# FOC_STM32G431.net
KiCad netlist of a schematic drawn in Altium Designer
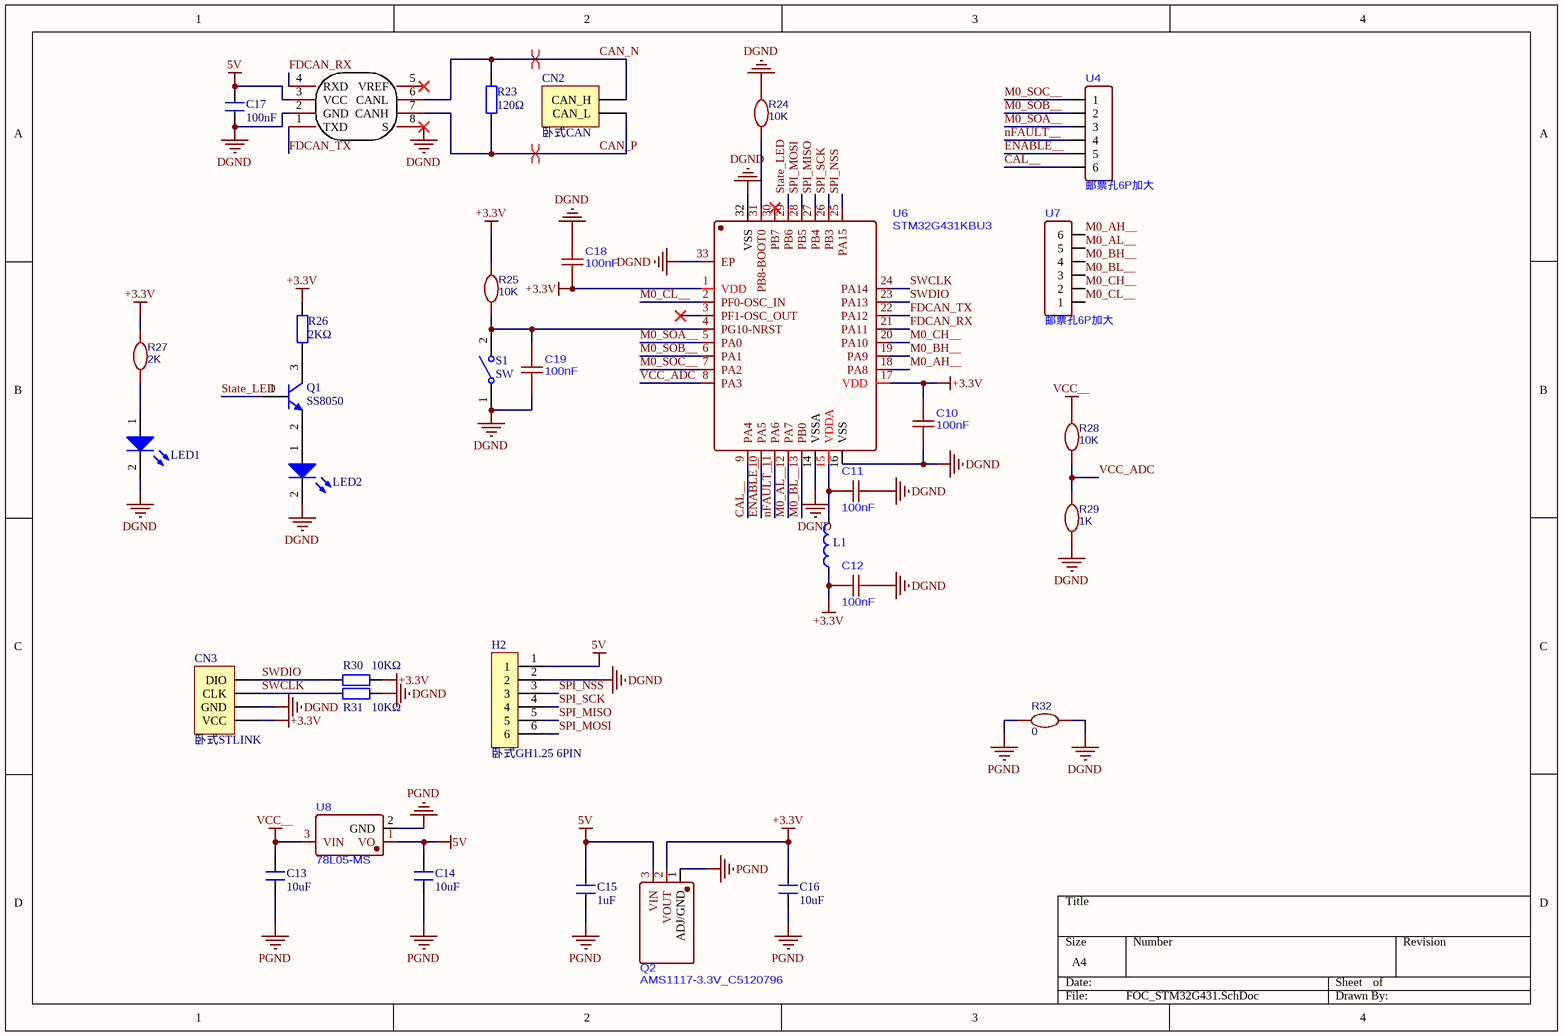
[diagram p0: FOC_STM32G431.SchDoc]

(export (version "E")
  (design (tool "Eeschema 10.0.6"))
  (components
    (comp (ref "C10") (value "100nF") (footprint "c0402") (libsource (lib "PETO") (part "CC0201JRX7R9BB101")))
    (comp (ref "C11") (value "100nF") (footprint "c0402") (libsource (lib "PETO") (part "CC0201JRX7R9BB101")))
    (comp (ref "C12") (value "100nF") (footprint "c0402") (libsource (lib "PETO") (part "CC0201JRX7R9BB101")))
    (comp (ref "C13")
      (value "10uF")
      (footprint "1210")
      (description "1210贴片电容")
      (libsource (lib "Integrated_Library1") (part "1210贴片电容"))
    )
    (comp (ref "C14")
      (value "10uF")
      (footprint "1210")
      (description "1210贴片电容")
      (libsource (lib "Integrated_Library1") (part "1210贴片电容"))
    )
    (comp (ref "C15")
      (value "1uF")
      (footprint "c0402")
      (description "贴片电容0402")
      (libsource (lib "Integrated_Library1") (part "0402贴片电容"))
    )
    (comp (ref "C16")
      (value "10uF")
      (footprint "1210")
      (description "1210贴片电容")
      (libsource (lib "Integrated_Library1") (part "1210贴片电容"))
    )
    (comp (ref "C17")
      (value "100nF")
      (footprint "c0402")
      (description "贴片电容0402")
      (libsource (lib "Integrated_Library1") (part "0402贴片电容"))
    )
    (comp (ref "C18") (value "100nF") (footprint "c0402") (libsource (lib "PETO") (part "CC0201JRX7R9BB101")))
    (comp (ref "C19") (value "100nF") (footprint "c0402") (libsource (lib "PETO") (part "CC0201JRX7R9BB101")))
    (comp (ref "CN2")
      (value "卧式CAN")
      (footprint "GH1.25 2P 卧式")
      (fields (field (name "PUBLISHER") "Altium Limited"))
      (libsource (lib "Integrated_Library1") (part "卧式CAN"))
    )
    (comp (ref "CN3")
      (value "卧式STLINK")
      (footprint "CONN-SMD_4P-P1.25_GH1.25-4P")
      (libsource (lib "Integrated_Library1") (part "卧式STLINK"))
    )
    (comp (ref "H2")
      (value "卧式GH1.25 6PIN")
      (footprint "CONN-SMD_6P-P1.25_XYECONN_XY-GH1.25-6A61")
      (libsource (lib "En") (part "卧式GH1.25 6PIN"))
    )
    (comp (ref "L1")
      (value "1008屏蔽电感")
      (footprint "R0603")
      (libsource (lib "Integrated_Library1") (part "1008屏蔽电感"))
    )
    (comp (ref "LED1")
      (value "LED")
      (footprint "led0805")
      (description "0805贴片LED")
      (libsource (lib "Integrated_Library1") (part "0805贴片LED"))
    )
    (comp (ref "LED2")
      (value "LED")
      (footprint "led0805")
      (description "0805贴片LED")
      (libsource (lib "Integrated_Library1") (part "0805贴片LED"))
    )
    (comp (ref "Q1")
      (value "SS8050")
      (footprint "SOT-23-3_L2.9-W1.3-P1.90-LS2.4-BR")
      (description "三极管")
      (libsource (lib "Integrated_Library1") (part "2N2222"))
    )
    (comp (ref "Q2")
      (value "AMS1117-3.3V_C5120796")
      (footprint "SOT-89-3_L4.5-W2.5-P1.50-LS4.2-BR")
      (libsource (lib "FOC_DRV8323") (part "AMS1117-3.3V_C5120796"))
    )
    (comp (ref "R23")
      (value "120Ω")
      (footprint "R0402")
      (description "0402贴片电阻")
      (libsource (lib "Integrated_Library1") (part "0402贴片电阻"))
    )
    (comp (ref "R24")
      (value "10K")
      (footprint "R0402")
      (fields
        (field (name "BOM_MANUFACTURER PART") "0603WAJ022JT5E")
        (field (name "BOM_SUPPLIER PART") "C25226")
      )
      (libsource (lib "altium-import") (part "root_3_2.2R_"))
    )
    (comp (ref "R25")
      (value "10K")
      (footprint "R0402")
      (fields
        (field (name "BOM_MANUFACTURER PART") "0603WAJ022JT5E")
        (field (name "BOM_SUPPLIER PART") "C25226")
      )
      (libsource (lib "altium-import") (part "root_3_2.2R_"))
    )
    (comp (ref "R26")
      (value "2KΩ")
      (footprint "R0402")
      (description "0402贴片电阻")
      (libsource (lib "Integrated_Library1") (part "0402贴片电阻"))
    )
    (comp (ref "R27")
      (value "2K")
      (footprint "R0402")
      (fields
        (field (name "BOM_MANUFACTURER PART") "0603WAJ022JT5E")
        (field (name "BOM_SUPPLIER PART") "C25226")
      )
      (libsource (lib "altium-import") (part "root_3_2.2R_"))
    )
    (comp (ref "R28")
      (value "10K")
      (footprint "R0402")
      (fields
        (field (name "BOM_MANUFACTURER PART") "0603WAJ022JT5E")
        (field (name "BOM_SUPPLIER PART") "C25226")
      )
      (libsource (lib "altium-import") (part "root_1_2.2R_"))
    )
    (comp (ref "R29")
      (value "1K")
      (footprint "R0402")
      (fields
        (field (name "BOM_MANUFACTURER PART") "0603WAJ022JT5E")
        (field (name "BOM_SUPPLIER PART") "C25226")
      )
      (libsource (lib "altium-import") (part "root_1_2.2R_"))
    )
    (comp (ref "R30")
      (value "10KΩ")
      (footprint "R0402")
      (description "0402贴片电阻")
      (libsource (lib "") (part "0402贴片电阻_1"))
    )
    (comp (ref "R31")
      (value "10KΩ")
      (footprint "R0402")
      (description "0402贴片电阻")
      (libsource (lib "") (part "0402贴片电阻_2"))
    )
    (comp (ref "R32")
      (value "0")
      (footprint "R0402")
      (fields
        (field (name "BOM_MANUFACTURER PART") "0603WAJ022JT5E")
        (field (name "BOM_SUPPLIER PART") "C25226")
      )
      (libsource (lib "altium-import") (part "root_0_2.2R_"))
    )
    (comp (ref "S1")
      (value "SW")
      (footprint "KEY_SMD")
      (description "开关")
      (libsource (lib "Integrated_Library1") (part "SW"))
    )
    (comp (ref "U4")
      (value "邮票孔6P加大")
      (footprint "PCBComponent_1 - duplicate")
      (libsource (lib "FOC_DRV8323") (part "邮票孔6P加大"))
    )
    (comp (ref "U5")
      (value "SN65HVD1050DR")
      (footprint "SOIC-8_L4.9-W3.9-P1.27-LS6.0-BL")
      (description "CAN芯片")
      (fields (field (name "MANUFACTURER") "TI(德州仪器)"))
      (libsource (lib "Integrated_Library1") (part "SN65HVD1050DR"))
    )
    (comp (ref "U6")
      (value "STM32G431KBU3")
      (footprint "UFQFPN-32_L5.0-W5.0-P0.50-BL-EP3.5")
      (libsource (lib "FOC_DRV8323") (part "STM32G431KBU3"))
    )
    (comp (ref "U7")
      (value "邮票孔6P加大")
      (footprint "PCBComponent_1 - duplicate")
      (libsource (lib "FOC_DRV8323") (part "邮票孔6P加大"))
    )
    (comp (ref "U8")
      (value "78L05-MS")
      (footprint "SOT-89-3_L4.5-W2.5-P1.50-LS4.2-BR")
      (libsource (lib "FOC_DRV8323") (part "78L05-MS"))
    )
  )
  (nets
    (net (code "1") (name "+3.3V") (class "Default")
      (node (ref "C10") (pin "2") (pinfunction "2_2") (pintype "passive"))
      (node (ref "C12") (pin "2") (pinfunction "2_2") (pintype "passive"))
      (node (ref "C16") (pin "2") (pinfunction "2_2") (pintype "passive"))
      (node (ref "C18") (pin "2") (pinfunction "2_2") (pintype "passive"))
      (node (ref "CN3") (pin "1") (pinfunction "VCC_1") (pintype "passive"))
      (node (ref "L1") (pin "1") (pinfunction "1_1") (pintype "passive"))
      (node (ref "Q2") (pin "2") (pinfunction "VOUT_2") (pintype "passive"))
      (node (ref "R25") (pin "1") (pinfunction "1_1") (pintype "passive"))
      (node (ref "R26") (pin "2") (pinfunction "2_2") (pintype "passive"))
      (node (ref "R27") (pin "1") (pinfunction "1_1") (pintype "passive"))
      (node (ref "R30") (pin "1") (pinfunction "1_1") (pintype "passive"))
      (node (ref "U6") (pin "1") (pinfunction "VDD_1") (pintype "passive"))
      (node (ref "U6") (pin "17") (pinfunction "VDD_17") (pintype "passive"))
    )
    (net (code "2") (name "/CAL__") (class "Default")
      (node (ref "U4") (pin "1") (pinfunction "6_1") (pintype "passive"))
      (node (ref "U6") (pin "9") (pinfunction "PA4_9") (pintype "passive"))
    )
    (net (code "3") (name "/CAN_N") (class "Default")
      (node (ref "CN2") (pin "1") (pinfunction "CAN_H_1") (pintype "passive"))
      (node (ref "R23") (pin "2") (pinfunction "2_2") (pintype "passive"))
      (node (ref "U5") (pin "6") (pinfunction "CANL_6") (pintype "passive"))
    )
    (net (code "4") (name "/CAN_P") (class "Default")
      (node (ref "CN2") (pin "2") (pinfunction "CAN_L_2") (pintype "passive"))
      (node (ref "R23") (pin "1") (pinfunction "1_1") (pintype "passive"))
      (node (ref "U5") (pin "7") (pinfunction "CANH_7") (pintype "passive"))
    )
    (net (code "5") (name "/ENABLE__") (class "Default")
      (node (ref "U4") (pin "2") (pinfunction "5_2") (pintype "passive"))
      (node (ref "U6") (pin "10") (pinfunction "PA5_10") (pintype "passive"))
    )
    (net (code "6") (name "/FDCAN_RX") (class "Default")
      (node (ref "U5") (pin "4") (pinfunction "RXD_4") (pintype "passive"))
      (node (ref "U6") (pin "21") (pinfunction "PA11_21") (pintype "passive"))
    )
    (net (code "7") (name "/FDCAN_TX") (class "Default")
      (node (ref "U5") (pin "1") (pinfunction "TXD_1") (pintype "passive"))
      (node (ref "U6") (pin "22") (pinfunction "PA12_22") (pintype "passive"))
    )
    (net (code "8") (name "/M0_AH__") (class "Default")
      (node (ref "U6") (pin "18") (pinfunction "PA8_18") (pintype "passive"))
      (node (ref "U7") (pin "1") (pinfunction "6_1") (pintype "passive"))
    )
    (net (code "9") (name "/M0_AL__") (class "Default")
      (node (ref "U6") (pin "12") (pinfunction "PA7_12") (pintype "passive"))
      (node (ref "U7") (pin "2") (pinfunction "5_2") (pintype "passive"))
    )
    (net (code "10") (name "/M0_BH__") (class "Default")
      (node (ref "U6") (pin "19") (pinfunction "PA9_19") (pintype "passive"))
      (node (ref "U7") (pin "3") (pinfunction "4_3") (pintype "passive"))
    )
    (net (code "11") (name "/M0_BL__") (class "Default")
      (node (ref "U6") (pin "13") (pinfunction "PB0_13") (pintype "passive"))
      (node (ref "U7") (pin "4") (pinfunction "3_4") (pintype "passive"))
    )
    (net (code "12") (name "/M0_CH__") (class "Default")
      (node (ref "U6") (pin "20") (pinfunction "PA10_20") (pintype "passive"))
      (node (ref "U7") (pin "5") (pinfunction "2_5") (pintype "passive"))
    )
    (net (code "13") (name "/M0_CL__") (class "Default")
      (node (ref "U6") (pin "2") (pinfunction "PF0-OSC_IN_2") (pintype "passive"))
      (node (ref "U7") (pin "6") (pinfunction "1_6") (pintype "passive"))
    )
    (net (code "14") (name "/M0_SOA__") (class "Default")
      (node (ref "U4") (pin "4") (pinfunction "3_4") (pintype "passive"))
      (node (ref "U6") (pin "5") (pinfunction "PA0_5") (pintype "passive"))
    )
    (net (code "15") (name "/M0_SOB__") (class "Default")
      (node (ref "U4") (pin "5") (pinfunction "2_5") (pintype "passive"))
      (node (ref "U6") (pin "6") (pinfunction "PA1_6") (pintype "passive"))
    )
    (net (code "16") (name "/M0_SOC__") (class "Default")
      (node (ref "U4") (pin "6") (pinfunction "1_6") (pintype "passive"))
      (node (ref "U6") (pin "7") (pinfunction "PA2_7") (pintype "passive"))
    )
    (net (code "17") (name "/SPI_MISO") (class "Default")
      (node (ref "H2") (pin "5") (pinfunction "5_5") (pintype "passive"))
      (node (ref "U6") (pin "27") (pinfunction "PB4_27") (pintype "passive"))
    )
    (net (code "18") (name "/SPI_MOSI") (class "Default")
      (node (ref "H2") (pin "6") (pinfunction "6_6") (pintype "passive"))
      (node (ref "U6") (pin "28") (pinfunction "PB5_28") (pintype "passive"))
    )
    (net (code "19") (name "/SPI_NSS") (class "Default")
      (node (ref "H2") (pin "3") (pinfunction "3_3") (pintype "passive"))
      (node (ref "U6") (pin "25") (pinfunction "PA15_25") (pintype "passive"))
    )
    (net (code "20") (name "/SPI_SCK") (class "Default")
      (node (ref "H2") (pin "4") (pinfunction "4_4") (pintype "passive"))
      (node (ref "U6") (pin "26") (pinfunction "PB3_26") (pintype "passive"))
    )
    (net (code "21") (name "/SWCLK") (class "Default")
      (node (ref "CN3") (pin "3") (pinfunction "CLK_3") (pintype "passive"))
      (node (ref "R31") (pin "1") (pinfunction "1_1") (pintype "passive"))
      (node (ref "U6") (pin "24") (pinfunction "PA14_24") (pintype "passive"))
    )
    (net (code "22") (name "/SWDIO") (class "Default")
      (node (ref "CN3") (pin "4") (pinfunction "DIO_4") (pintype "passive"))
      (node (ref "R30") (pin "2") (pinfunction "2_2") (pintype "passive"))
      (node (ref "U6") (pin "23") (pinfunction "PA13_23") (pintype "passive"))
    )
    (net (code "23") (name "/State_LED") (class "Default")
      (node (ref "Q1") (pin "1") (pinfunction "B_1") (pintype "passive"))
      (node (ref "U6") (pin "29") (pinfunction "PB6_29") (pintype "passive"))
    )
    (net (code "24") (name "/VCC_ADC") (class "Default")
      (node (ref "R28") (pin "1") (pinfunction "1_1") (pintype "passive"))
      (node (ref "R29") (pin "2") (pinfunction "2_2") (pintype "passive"))
      (node (ref "U6") (pin "8") (pinfunction "PA3_8") (pintype "passive"))
    )
    (net (code "25") (name "/nFAULT__") (class "Default")
      (node (ref "U4") (pin "3") (pinfunction "4_3") (pintype "passive"))
      (node (ref "U6") (pin "11") (pinfunction "PA6_11") (pintype "passive"))
    )
    (net (code "26") (name "5V") (class "Default")
      (node (ref "C14") (pin "2") (pinfunction "2_2") (pintype "passive"))
      (node (ref "C15") (pin "2") (pinfunction "2_2") (pintype "passive"))
      (node (ref "C17") (pin "2") (pinfunction "2_2") (pintype "passive"))
      (node (ref "H2") (pin "1") (pinfunction "1_1") (pintype "passive"))
      (node (ref "Q2") (pin "3") (pinfunction "VIN_3") (pintype "passive"))
      (node (ref "U5") (pin "3") (pinfunction "VCC_3") (pintype "passive"))
      (node (ref "U8") (pin "1") (pinfunction "VO_1") (pintype "passive"))
    )
    (net (code "27") (name "DGND") (class "Default")
      (node (ref "C10") (pin "1") (pinfunction "1_1") (pintype "passive"))
      (node (ref "C11") (pin "1") (pinfunction "1_1") (pintype "passive"))
      (node (ref "C12") (pin "1") (pinfunction "1_1") (pintype "passive"))
      (node (ref "C17") (pin "1") (pinfunction "1_1") (pintype "passive"))
      (node (ref "C18") (pin "1") (pinfunction "1_1") (pintype "passive"))
      (node (ref "C19") (pin "1") (pinfunction "1_1") (pintype "passive"))
      (node (ref "CN3") (pin "2") (pinfunction "GND_2") (pintype "passive"))
      (node (ref "H2") (pin "2") (pinfunction "2_2") (pintype "passive"))
      (node (ref "LED1") (pin "2") (pinfunction "K_2") (pintype "passive"))
      (node (ref "LED2") (pin "2") (pinfunction "K_2") (pintype "passive"))
      (node (ref "R24") (pin "1") (pinfunction "1_1") (pintype "passive"))
      (node (ref "R29") (pin "1") (pinfunction "1_1") (pintype "passive"))
      (node (ref "R31") (pin "2") (pinfunction "2_2") (pintype "passive"))
      (node (ref "R32") (pin "2") (pinfunction "2_2") (pintype "passive"))
      (node (ref "S1") (pin "1") (pinfunction "COMMON_1") (pintype "passive"))
      (node (ref "U5") (pin "2") (pinfunction "GND_2") (pintype "passive"))
      (node (ref "U5") (pin "8") (pinfunction "S_8") (pintype "passive"))
      (node (ref "U6") (pin "14") (pinfunction "VSSA_14") (pintype "passive"))
      (node (ref "U6") (pin "16") (pinfunction "VSS_16") (pintype "passive"))
      (node (ref "U6") (pin "32") (pinfunction "VSS_32") (pintype "passive"))
      (node (ref "U6") (pin "33") (pinfunction "EP_33") (pintype "passive"))
    )
    (net (code "28") (name "Net-(LED1-A)") (class "Default")
      (node (ref "LED1") (pin "1") (pinfunction "A_1") (pintype "passive"))
      (node (ref "R27") (pin "2") (pinfunction "2_2") (pintype "passive"))
    )
    (net (code "29") (name "Net-(LED2-A)") (class "Default")
      (node (ref "LED2") (pin "1") (pinfunction "A_1") (pintype "passive"))
      (node (ref "Q1") (pin "2") (pinfunction "E_2") (pintype "passive"))
    )
    (net (code "30") (name "Net-(Q1-C)") (class "Default")
      (node (ref "Q1") (pin "3") (pinfunction "C_3") (pintype "passive"))
      (node (ref "R26") (pin "1") (pinfunction "1_1") (pintype "passive"))
    )
    (net (code "31") (name "Net-(S1-NO)") (class "Default")
      (node (ref "C19") (pin "2") (pinfunction "2_2") (pintype "passive"))
      (node (ref "R25") (pin "2") (pinfunction "2_2") (pintype "passive"))
      (node (ref "S1") (pin "2") (pinfunction "NO_2") (pintype "passive"))
      (node (ref "U6") (pin "4") (pinfunction "PG10-NRST_4") (pintype "passive"))
    )
    (net (code "32") (name "Net-(U6-PB8-BOOT0)") (class "Default")
      (node (ref "R24") (pin "2") (pinfunction "2_2") (pintype "passive"))
      (node (ref "U6") (pin "31") (pinfunction "PB8-BOOT0_31") (pintype "passive"))
    )
    (net (code "33") (name "Net-(U6-VDDA)") (class "Default")
      (node (ref "C11") (pin "2") (pinfunction "2_2") (pintype "passive"))
      (node (ref "L1") (pin "2") (pinfunction "2_2") (pintype "passive"))
      (node (ref "U6") (pin "15") (pinfunction "VDDA_15") (pintype "passive"))
    )
    (net (code "34") (name "PGND") (class "Default")
      (node (ref "C13") (pin "1") (pinfunction "1_1") (pintype "passive"))
      (node (ref "C14") (pin "1") (pinfunction "1_1") (pintype "passive"))
      (node (ref "C15") (pin "1") (pinfunction "1_1") (pintype "passive"))
      (node (ref "C16") (pin "1") (pinfunction "1_1") (pintype "passive"))
      (node (ref "Q2") (pin "1") (pinfunction "ADJ/GND_1") (pintype "passive"))
      (node (ref "R32") (pin "1") (pinfunction "1_1") (pintype "passive"))
      (node (ref "U8") (pin "2") (pinfunction "GND_2") (pintype "passive"))
    )
    (net (code "35") (name "VCC__") (class "Default")
      (node (ref "C13") (pin "2") (pinfunction "2_2") (pintype "passive"))
      (node (ref "R28") (pin "2") (pinfunction "2_2") (pintype "passive"))
      (node (ref "U8") (pin "3") (pinfunction "VIN_3") (pintype "passive"))
    )
    (net (code "36") (name "unconnected-(U5-VREF-Pad5)") (class "Default")
      (node (ref "U5") (pin "5") (pinfunction "VREF_5") (pintype "passive+no_connect"))
    )
    (net (code "37") (name "unconnected-(U6-PB7-Pad30)") (class "Default")
      (node (ref "U6") (pin "30") (pinfunction "PB7_30") (pintype "passive+no_connect"))
    )
    (net (code "38") (name "unconnected-(U6-PF1-OSC_OUT-Pad3)") (class "Default")
      (node (ref "U6") (pin "3") (pinfunction "PF1-OSC_OUT_3") (pintype "passive+no_connect"))
    )
  )
)
